# CHRONGLER.net
KiCad netlist of a schematic drawn in EAGLE
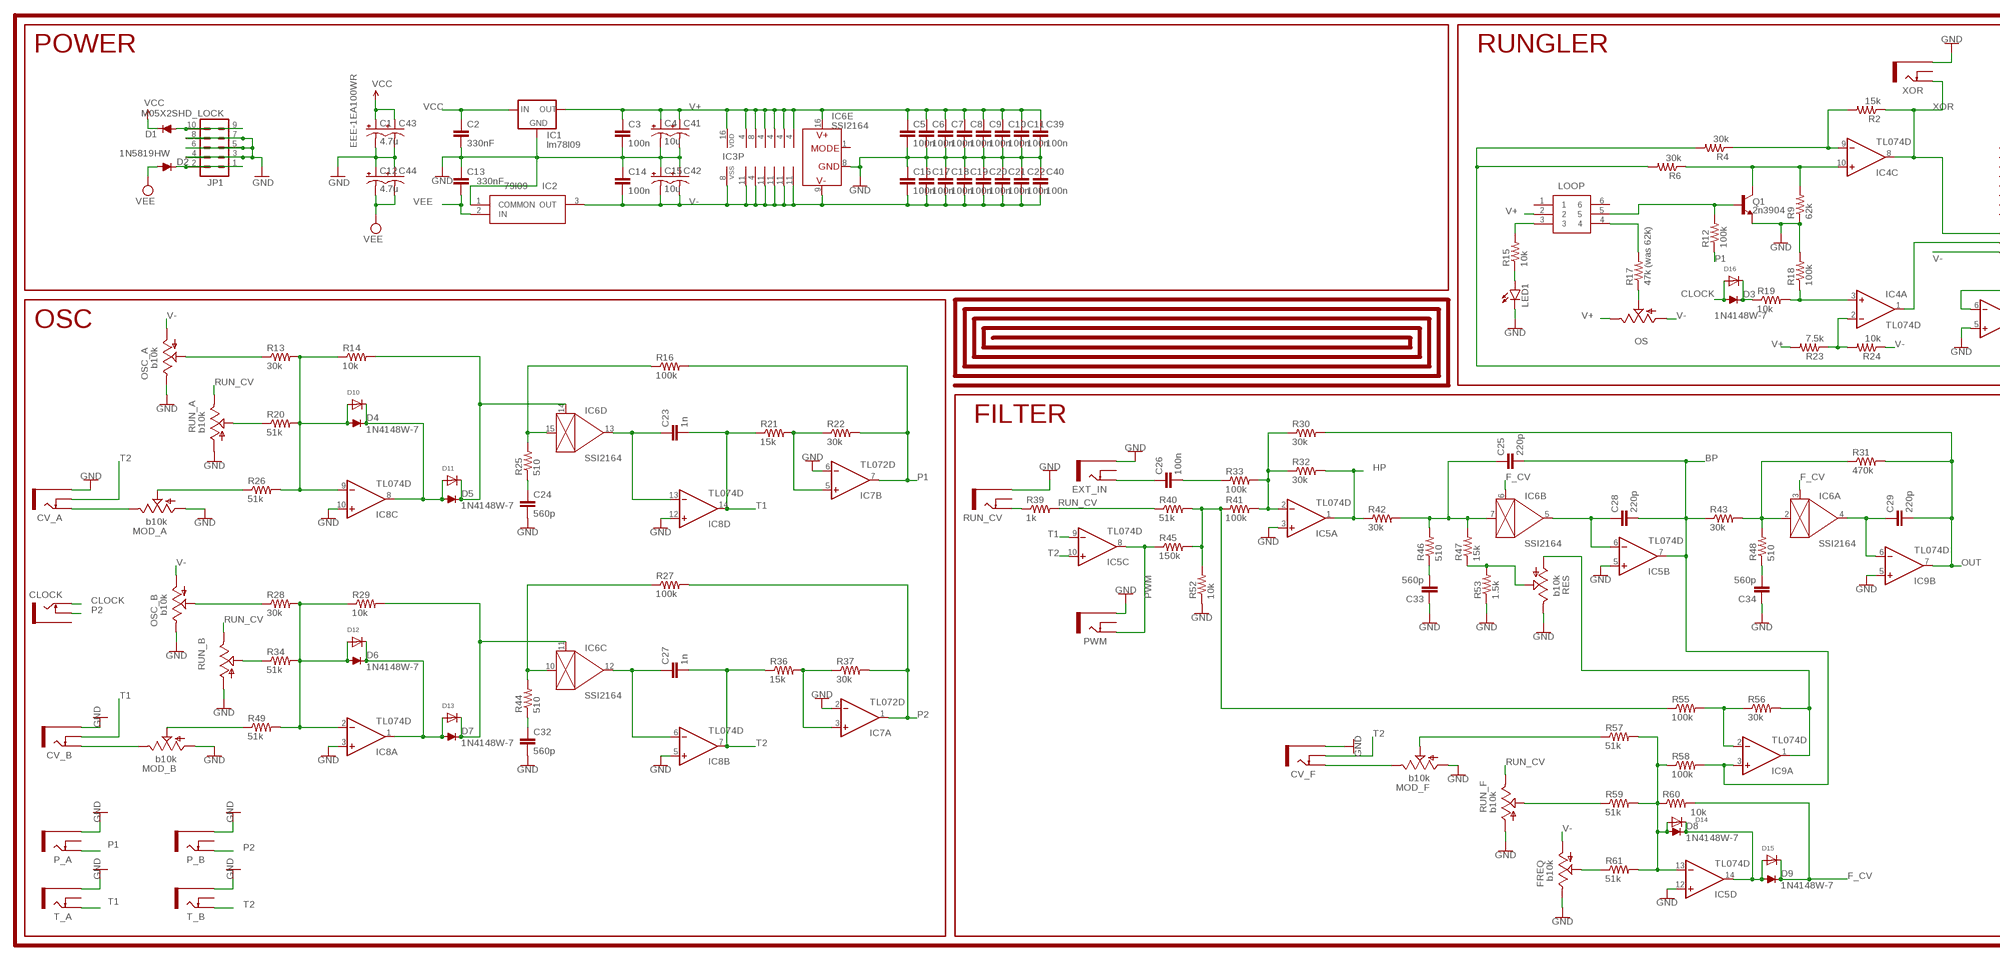
[diagram p0: schematic, sheet 1, part 1 of 2]
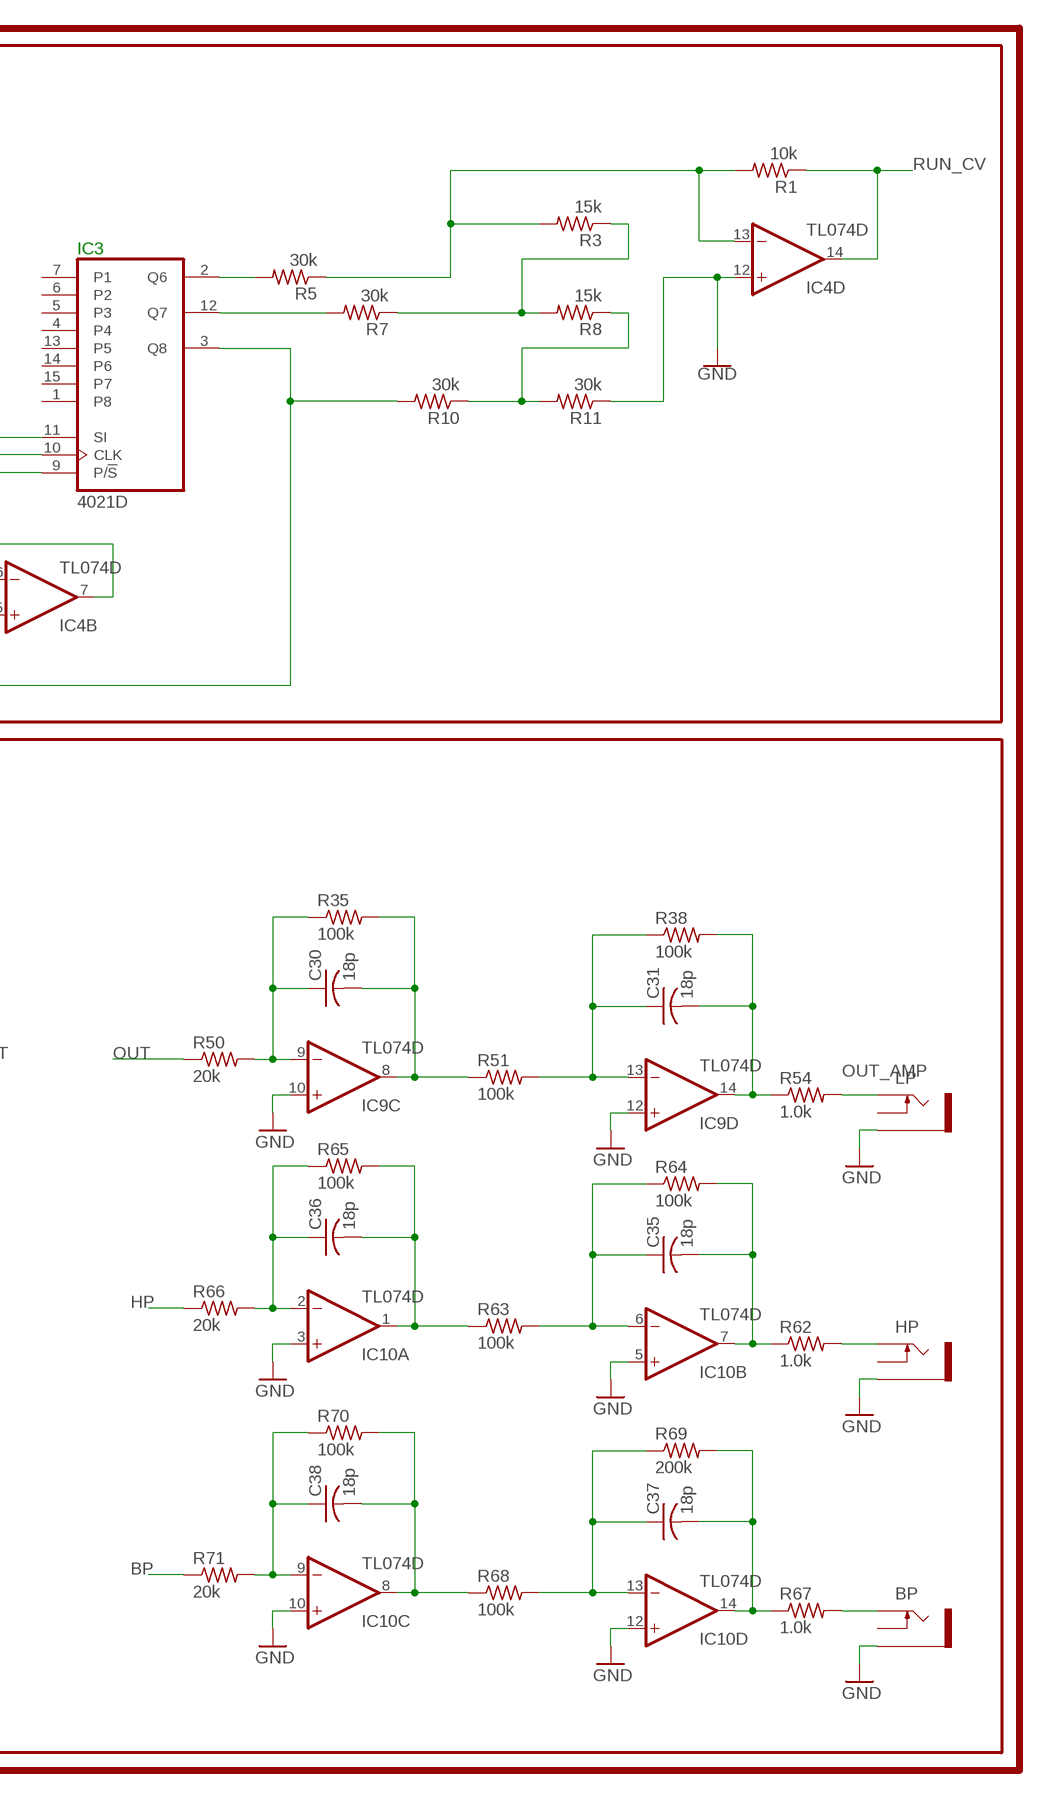
[diagram p1: schematic, sheet 1, part 2 of 2]

(export (version "E")
  (design (tool "Eeschema 10.0.6"))
  (components
    (comp (ref "BP")
      (value "THONKICONNNEW")
      (footprint "eagle-import:WQP-PJ301M-12_JACK")
      (libsource (lib "eagle-import") (part "THONKICONNNEW"))
    )
    (comp (ref "C1")
      (value "4.7u")
      (footprint "eagle-import:PANASONIC_C")
      (libsource (lib "eagle-import") (part "rcl_CPOL-USC"))
    )
    (comp (ref "C2")
      (value "330nF")
      (footprint "eagle-import:C1206")
      (libsource (lib "eagle-import") (part "C-EUC1206"))
    )
    (comp (ref "C3")
      (value "100n")
      (footprint "eagle-import:C1206")
      (libsource (lib "eagle-import") (part "C-EUC1206"))
    )
    (comp (ref "C4")
      (value "10u")
      (footprint "eagle-import:PANASONIC_C")
      (libsource (lib "eagle-import") (part "rcl_CPOL-USC"))
    )
    (comp (ref "C5")
      (value "100n")
      (footprint "eagle-import:C0603")
      (libsource (lib "eagle-import") (part "C-EUC0603"))
    )
    (comp (ref "C6")
      (value "100n")
      (footprint "eagle-import:C0603")
      (libsource (lib "eagle-import") (part "C-EUC0603"))
    )
    (comp (ref "C7")
      (value "100n")
      (footprint "eagle-import:C0603")
      (libsource (lib "eagle-import") (part "C-EUC0603"))
    )
    (comp (ref "C8")
      (value "100n")
      (footprint "eagle-import:C0603")
      (libsource (lib "eagle-import") (part "C-EUC0603"))
    )
    (comp (ref "C9")
      (value "100n")
      (footprint "eagle-import:C0603")
      (libsource (lib "eagle-import") (part "C-EUC0603"))
    )
    (comp (ref "C10")
      (value "100n")
      (footprint "eagle-import:C0603")
      (libsource (lib "eagle-import") (part "C-EUC0603"))
    )
    (comp (ref "C11")
      (value "100n")
      (footprint "eagle-import:C0603")
      (libsource (lib "eagle-import") (part "C-EUC0603"))
    )
    (comp (ref "C12")
      (value "4.7u")
      (footprint "eagle-import:PANASONIC_C")
      (libsource (lib "eagle-import") (part "rcl_CPOL-USC"))
    )
    (comp (ref "C13")
      (value "330nF")
      (footprint "eagle-import:C1206")
      (libsource (lib "eagle-import") (part "C-EUC1206"))
    )
    (comp (ref "C14")
      (value "100n")
      (footprint "eagle-import:C1206")
      (libsource (lib "eagle-import") (part "C-EUC1206"))
    )
    (comp (ref "C15")
      (value "10u")
      (footprint "eagle-import:PANASONIC_C")
      (libsource (lib "eagle-import") (part "rcl_CPOL-USC"))
    )
    (comp (ref "C16")
      (value "100n")
      (footprint "eagle-import:C0603")
      (libsource (lib "eagle-import") (part "C-EUC0603"))
    )
    (comp (ref "C17")
      (value "100n")
      (footprint "eagle-import:C0603")
      (libsource (lib "eagle-import") (part "C-EUC0603"))
    )
    (comp (ref "C18")
      (value "100n")
      (footprint "eagle-import:C0603")
      (libsource (lib "eagle-import") (part "C-EUC0603"))
    )
    (comp (ref "C19")
      (value "100n")
      (footprint "eagle-import:C0603")
      (libsource (lib "eagle-import") (part "C-EUC0603"))
    )
    (comp (ref "C20")
      (value "100n")
      (footprint "eagle-import:C0603")
      (libsource (lib "eagle-import") (part "C-EUC0603"))
    )
    (comp (ref "C21")
      (value "100n")
      (footprint "eagle-import:C0603")
      (libsource (lib "eagle-import") (part "C-EUC0603"))
    )
    (comp (ref "C22")
      (value "100n")
      (footprint "eagle-import:C0603")
      (libsource (lib "eagle-import") (part "C-EUC0603"))
    )
    (comp (ref "C23")
      (value "1n")
      (footprint "eagle-import:C0603")
      (libsource (lib "eagle-import") (part "C-EUC0603"))
    )
    (comp (ref "C24")
      (value "560p")
      (footprint "eagle-import:C0603")
      (libsource (lib "eagle-import") (part "C-EUC0603"))
    )
    (comp (ref "C25")
      (value "220p")
      (footprint "eagle-import:C0603")
      (libsource (lib "eagle-import") (part "C-EUC0603"))
    )
    (comp (ref "C26")
      (value "100n")
      (footprint "eagle-import:C0603")
      (libsource (lib "eagle-import") (part "C-EUC0603"))
    )
    (comp (ref "C27")
      (value "1n")
      (footprint "eagle-import:C0603")
      (libsource (lib "eagle-import") (part "C-EUC0603"))
    )
    (comp (ref "C28")
      (value "220p")
      (footprint "eagle-import:C0603")
      (libsource (lib "eagle-import") (part "C-EUC0603"))
    )
    (comp (ref "C29")
      (value "220p")
      (footprint "eagle-import:C0603")
      (libsource (lib "eagle-import") (part "C-EUC0603"))
    )
    (comp (ref "C30")
      (value "18p")
      (footprint "eagle-import:C0603")
      (libsource (lib "eagle-import") (part "C-USC0603"))
    )
    (comp (ref "C31")
      (value "18p")
      (footprint "eagle-import:C0603")
      (libsource (lib "eagle-import") (part "C-USC0603"))
    )
    (comp (ref "C32")
      (value "560p")
      (footprint "eagle-import:C0603")
      (libsource (lib "eagle-import") (part "C-EUC0603"))
    )
    (comp (ref "C33")
      (value "560p")
      (footprint "eagle-import:C0603")
      (libsource (lib "eagle-import") (part "C-EUC0603"))
    )
    (comp (ref "C34")
      (value "560p")
      (footprint "eagle-import:C0603")
      (libsource (lib "eagle-import") (part "C-EUC0603"))
    )
    (comp (ref "C35")
      (value "18p")
      (footprint "eagle-import:C0603")
      (libsource (lib "eagle-import") (part "C-USC0603"))
    )
    (comp (ref "C36")
      (value "18p")
      (footprint "eagle-import:C0603")
      (libsource (lib "eagle-import") (part "C-USC0603"))
    )
    (comp (ref "C37")
      (value "18p")
      (footprint "eagle-import:C0603")
      (libsource (lib "eagle-import") (part "C-USC0603"))
    )
    (comp (ref "C38")
      (value "18p")
      (footprint "eagle-import:C0603")
      (libsource (lib "eagle-import") (part "C-USC0603"))
    )
    (comp (ref "C39")
      (value "100n")
      (footprint "eagle-import:C0603")
      (libsource (lib "eagle-import") (part "C-EUC0603"))
    )
    (comp (ref "C40")
      (value "100n")
      (footprint "eagle-import:C0603")
      (libsource (lib "eagle-import") (part "C-EUC0603"))
    )
    (comp (ref "C41")
      (value "CPOL-USE2.5-6")
      (footprint "eagle-import:E2,5-6")
      (libsource (lib "eagle-import") (part "CPOL-USE2.5-6"))
    )
    (comp (ref "C42")
      (value "CPOL-USE2.5-6")
      (footprint "eagle-import:E2,5-6")
      (libsource (lib "eagle-import") (part "CPOL-USE2.5-6"))
    )
    (comp (ref "C43")
      (value "CPOL-USE2.5-6")
      (footprint "eagle-import:E2,5-6")
      (libsource (lib "eagle-import") (part "CPOL-USE2.5-6"))
    )
    (comp (ref "C44")
      (value "CPOL-USE2.5-6")
      (footprint "eagle-import:E2,5-6")
      (libsource (lib "eagle-import") (part "CPOL-USE2.5-6"))
    )
    (comp (ref "CLOCK")
      (value "THONKICONNNEW")
      (footprint "eagle-import:WQP-PJ301M-12_JACK")
      (libsource (lib "eagle-import") (part "THONKICONNNEW"))
    )
    (comp (ref "CV_A")
      (value "THONKICONNNEW")
      (footprint "eagle-import:WQP-PJ301M-12_JACK")
      (libsource (lib "eagle-import") (part "THONKICONNNEW"))
    )
    (comp (ref "CV_B")
      (value "THONKICONNNEW")
      (footprint "eagle-import:WQP-PJ301M-12_JACK")
      (libsource (lib "eagle-import") (part "THONKICONNNEW"))
    )
    (comp (ref "CV_F")
      (value "THONKICONNNEW")
      (footprint "eagle-import:WQP-PJ301M-12_JACK")
      (libsource (lib "eagle-import") (part "THONKICONNNEW"))
    )
    (comp (ref "D1")
      (value "1N5819HW")
      (footprint "eagle-import:SOD123")
      (libsource (lib "eagle-import") (part "DIODE-SOD123"))
    )
    (comp (ref "D2")
      (value "1N5819HW")
      (footprint "eagle-import:SOD123")
      (libsource (lib "eagle-import") (part "DIODE-SOD123"))
    )
    (comp (ref "D3")
      (value "1N4148W-7")
      (footprint "eagle-import:SOD123")
      (libsource (lib "eagle-import") (part "1N4148W-7"))
    )
    (comp (ref "D4")
      (value "1N4148W-7")
      (footprint "eagle-import:SOD123")
      (libsource (lib "eagle-import") (part "1N4148W-7"))
    )
    (comp (ref "D5")
      (value "1N4148W-7")
      (footprint "eagle-import:SOD123")
      (libsource (lib "eagle-import") (part "1N4148W-7"))
    )
    (comp (ref "D6")
      (value "1N4148W-7")
      (footprint "eagle-import:SOD123")
      (libsource (lib "eagle-import") (part "1N4148W-7"))
    )
    (comp (ref "D7")
      (value "1N4148W-7")
      (footprint "eagle-import:SOD123")
      (libsource (lib "eagle-import") (part "1N4148W-7"))
    )
    (comp (ref "D8")
      (value "1N4148W-7")
      (footprint "eagle-import:SOD123")
      (libsource (lib "eagle-import") (part "1N4148W-7"))
    )
    (comp (ref "D9")
      (value "1N4148W-7")
      (footprint "eagle-import:SOD123")
      (libsource (lib "eagle-import") (part "1N4148W-7"))
    )
    (comp (ref "D10")
      (value "DIODESOD-323F")
      (footprint "eagle-import:SOD-323F")
      (libsource (lib "eagle-import") (part "DIODESOD-323F"))
    )
    (comp (ref "D11")
      (value "DIODESOD-323F")
      (footprint "eagle-import:SOD-323F")
      (libsource (lib "eagle-import") (part "DIODESOD-323F"))
    )
    (comp (ref "D12")
      (value "DIODESOD-323F")
      (footprint "eagle-import:SOD-323F")
      (libsource (lib "eagle-import") (part "DIODESOD-323F"))
    )
    (comp (ref "D13")
      (value "DIODESOD-323F")
      (footprint "eagle-import:SOD-323F")
      (libsource (lib "eagle-import") (part "DIODESOD-323F"))
    )
    (comp (ref "D14")
      (value "DIODESOD-323F")
      (footprint "eagle-import:SOD-323F")
      (libsource (lib "eagle-import") (part "DIODESOD-323F"))
    )
    (comp (ref "D15")
      (value "DIODESOD-323F")
      (footprint "eagle-import:SOD-323F")
      (libsource (lib "eagle-import") (part "DIODESOD-323F"))
    )
    (comp (ref "D16")
      (value "DIODESOD-323F")
      (footprint "eagle-import:SOD-323F")
      (libsource (lib "eagle-import") (part "DIODESOD-323F"))
    )
    (comp (ref "EXT_IN")
      (value "THONKICONNNEW")
      (footprint "eagle-import:WQP-PJ301M-12_JACK")
      (libsource (lib "eagle-import") (part "THONKICONNNEW"))
    )
    (comp (ref "FREQ")
      (value "b10k")
      (footprint "eagle-import:9MM_SNAP-IN_POT")
      (libsource (lib "eagle-import") (part "9MM_SNAP-IN_POT_"))
    )
    (comp (ref "HP")
      (value "THONKICONNNEW")
      (footprint "eagle-import:WQP-PJ301M-12_JACK")
      (libsource (lib "eagle-import") (part "THONKICONNNEW"))
    )
    (comp (ref "IC1")
      (value "lm78l09")
      (footprint "eagle-import:SOT89")
      (libsource (lib "eagle-import") (part "78LXX-SOT89"))
    )
    (comp (ref "IC2")
      (value "79l09")
      (footprint "eagle-import:SOT-89-3")
      (fields
        (field (name "MANUFACTURER_PART_NUMBER") "NJM79L05UA-TE1")
        (field (name "MOUSER_PART_NUMBER") "513-NJM79L05UA-TE1")
      )
      (libsource (lib "eagle-import") (part "NJM79L05UA-TE1"))
    )
    (comp (ref "IC3")
      (value "4021D")
      (footprint "eagle-import:SO16")
      (libsource (lib "eagle-import") (part "4021D"))
    )
    (comp (ref "IC4")
      (value "TL074D")
      (footprint "eagle-import:SO14")
      (libsource (lib "eagle-import") (part "TL074D"))
    )
    (comp (ref "IC5")
      (value "TL074D")
      (footprint "eagle-import:SO14")
      (libsource (lib "eagle-import") (part "TL074D"))
    )
    (comp (ref "IC6")
      (value "SSI2164")
      (footprint "eagle-import:SOIC16N")
      (libsource (lib "eagle-import") (part "SSM2164S"))
    )
    (comp (ref "IC7")
      (value "TL072D")
      (footprint "eagle-import:SO08")
      (libsource (lib "eagle-import") (part "TL072D"))
    )
    (comp (ref "IC8")
      (value "TL074D")
      (footprint "eagle-import:SO14")
      (libsource (lib "eagle-import") (part "TL074D"))
    )
    (comp (ref "IC9")
      (value "TL074D")
      (footprint "eagle-import:SO14")
      (libsource (lib "eagle-import") (part "TL074D"))
    )
    (comp (ref "IC10")
      (value "TL074D")
      (footprint "eagle-import:SO14")
      (libsource (lib "eagle-import") (part "TL074D"))
    )
    (comp (ref "JP1")
      (value "M05X2SHD_LOCK")
      (footprint "eagle-import:2X5-SHROUDED_LOCK")
      (libsource (lib "eagle-import") (part "M05X2SHD_LOCK"))
    )
    (comp (ref "LED1")
      (value "LEDLD260")
      (footprint "eagle-import:LD260")
      (libsource (lib "eagle-import") (part "LEDLD260"))
    )
    (comp (ref "LOOP")
      (value "MHPS2266")
      (footprint "eagle-import:DIPS450W80P200L600H1050Q6N")
      (fields (field (name "MOUSER_PART_NUMBER") "642-MHPS2266"))
      (libsource (lib "eagle-import") (part "MHPS2266"))
    )
    (comp (ref "LP")
      (value "THONKICONNNEW")
      (footprint "eagle-import:WQP-PJ301M-12_JACK")
      (libsource (lib "eagle-import") (part "THONKICONNNEW"))
    )
    (comp (ref "MOD_A")
      (value "b10k")
      (footprint "eagle-import:9MM_SNAP-IN_POT")
      (libsource (lib "eagle-import") (part "9MM_SNAP-IN_POT_"))
    )
    (comp (ref "MOD_B")
      (value "b10k")
      (footprint "eagle-import:9MM_SNAP-IN_POT")
      (libsource (lib "eagle-import") (part "9MM_SNAP-IN_POT_"))
    )
    (comp (ref "MOD_F")
      (value "b10k")
      (footprint "eagle-import:9MM_SNAP-IN_POT")
      (libsource (lib "eagle-import") (part "9MM_SNAP-IN_POT_"))
    )
    (comp (ref "OS")
      (value "9MM_SNAP-IN_POT_")
      (footprint "eagle-import:9MM_SNAP-IN_POT")
      (libsource (lib "eagle-import") (part "9MM_SNAP-IN_POT_"))
    )
    (comp (ref "OSC_A")
      (value "b10k")
      (footprint "eagle-import:9MM_SNAP-IN_POT")
      (libsource (lib "eagle-import") (part "9MM_SNAP-IN_POT_"))
    )
    (comp (ref "OSC_B")
      (value "b10k")
      (footprint "eagle-import:9MM_SNAP-IN_POT")
      (libsource (lib "eagle-import") (part "9MM_SNAP-IN_POT_"))
    )
    (comp (ref "PWM")
      (value "THONKICONNNEW")
      (footprint "eagle-import:WQP-PJ301M-12_JACK")
      (libsource (lib "eagle-import") (part "THONKICONNNEW"))
    )
    (comp (ref "P_A")
      (value "THONKICONNNEW")
      (footprint "eagle-import:WQP-PJ301M-12_JACK")
      (libsource (lib "eagle-import") (part "THONKICONNNEW"))
    )
    (comp (ref "P_B")
      (value "THONKICONNNEW")
      (footprint "eagle-import:WQP-PJ301M-12_JACK")
      (libsource (lib "eagle-import") (part "THONKICONNNEW"))
    )
    (comp (ref "Q1")
      (value "2n3904")
      (footprint "eagle-import:SOT23-3")
      (libsource (lib "eagle-import") (part "TRANS_NPN-MMBT2222AL"))
    )
    (comp (ref "R1")
      (value "10k")
      (footprint "eagle-import:R0603")
      (libsource (lib "eagle-import") (part "resistor_348_R-US_R0603"))
    )
    (comp (ref "R2")
      (value "15k")
      (footprint "eagle-import:R0603")
      (libsource (lib "eagle-import") (part "resistor_348_R-US_R0603"))
    )
    (comp (ref "R3")
      (value "15k")
      (footprint "eagle-import:R0603")
      (libsource (lib "eagle-import") (part "resistor_348_R-US_R0603"))
    )
    (comp (ref "R4")
      (value "30k")
      (footprint "eagle-import:R0603")
      (libsource (lib "eagle-import") (part "resistor_348_R-US_R0603"))
    )
    (comp (ref "R5")
      (value "30k")
      (footprint "eagle-import:R0603")
      (libsource (lib "eagle-import") (part "resistor_348_R-US_R0603"))
    )
    (comp (ref "R6")
      (value "30k")
      (footprint "eagle-import:R0603")
      (libsource (lib "eagle-import") (part "resistor_348_R-US_R0603"))
    )
    (comp (ref "R7")
      (value "30k")
      (footprint "eagle-import:R0603")
      (libsource (lib "eagle-import") (part "resistor_348_R-US_R0603"))
    )
    (comp (ref "R8")
      (value "15k")
      (footprint "eagle-import:R0603")
      (libsource (lib "eagle-import") (part "resistor_348_R-US_R0603"))
    )
    (comp (ref "R9")
      (value "62k")
      (footprint "eagle-import:R0603")
      (libsource (lib "eagle-import") (part "resistor_348_R-US_R0603"))
    )
    (comp (ref "R10")
      (value "30k")
      (footprint "eagle-import:R0603")
      (libsource (lib "eagle-import") (part "resistor_348_R-US_R0603"))
    )
    (comp (ref "R11")
      (value "30k")
      (footprint "eagle-import:R0603")
      (libsource (lib "eagle-import") (part "resistor_348_R-US_R0603"))
    )
    (comp (ref "R12")
      (value "100k")
      (footprint "eagle-import:R0603")
      (libsource (lib "eagle-import") (part "resistor_348_R-US_R0603"))
    )
    (comp (ref "R13")
      (value "30k")
      (footprint "eagle-import:R0603")
      (libsource (lib "eagle-import") (part "resistor_348_R-US_R0603"))
    )
    (comp (ref "R14")
      (value "10k")
      (footprint "eagle-import:R0603")
      (libsource (lib "eagle-import") (part "resistor_348_R-US_R0603"))
    )
    (comp (ref "R15")
      (value "10k")
      (footprint "eagle-import:R0603")
      (libsource (lib "eagle-import") (part "resistor_348_R-US_R0603"))
    )
    (comp (ref "R16")
      (value "100k")
      (footprint "eagle-import:R0603")
      (libsource (lib "eagle-import") (part "resistor_348_R-US_R0603"))
    )
    (comp (ref "R17")
      (value "47k (was 62k)")
      (footprint "eagle-import:R0603")
      (libsource (lib "eagle-import") (part "resistor_348_R-US_R0603"))
    )
    (comp (ref "R18")
      (value "100k")
      (footprint "eagle-import:R0603")
      (libsource (lib "eagle-import") (part "resistor_348_R-US_R0603"))
    )
    (comp (ref "R19")
      (value "10k")
      (footprint "eagle-import:R0603")
      (libsource (lib "eagle-import") (part "resistor_348_R-US_R0603"))
    )
    (comp (ref "R20")
      (value "51k")
      (footprint "eagle-import:R0603")
      (libsource (lib "eagle-import") (part "resistor_348_R-US_R0603"))
    )
    (comp (ref "R21")
      (value "15k")
      (footprint "eagle-import:R0603")
      (libsource (lib "eagle-import") (part "resistor_348_R-US_R0603"))
    )
    (comp (ref "R22")
      (value "30k")
      (footprint "eagle-import:R0603")
      (libsource (lib "eagle-import") (part "resistor_348_R-US_R0603"))
    )
    (comp (ref "R23")
      (value "7.5k")
      (footprint "eagle-import:R0603")
      (libsource (lib "eagle-import") (part "resistor_348_R-US_R0603"))
    )
    (comp (ref "R24")
      (value "10k")
      (footprint "eagle-import:R0603")
      (libsource (lib "eagle-import") (part "resistor_348_R-US_R0603"))
    )
    (comp (ref "R25")
      (value "510")
      (footprint "eagle-import:R0603")
      (libsource (lib "eagle-import") (part "resistor_348_R-US_R0603"))
    )
    (comp (ref "R26")
      (value "51k")
      (footprint "eagle-import:R0603")
      (libsource (lib "eagle-import") (part "resistor_348_R-US_R0603"))
    )
    (comp (ref "R27")
      (value "100k")
      (footprint "eagle-import:R0603")
      (libsource (lib "eagle-import") (part "resistor_348_R-US_R0603"))
    )
    (comp (ref "R28")
      (value "30k")
      (footprint "eagle-import:R0603")
      (libsource (lib "eagle-import") (part "resistor_348_R-US_R0603"))
    )
    (comp (ref "R29")
      (value "10k")
      (footprint "eagle-import:R0603")
      (libsource (lib "eagle-import") (part "resistor_348_R-US_R0603"))
    )
    (comp (ref "R30")
      (value "30k")
      (footprint "eagle-import:R0603")
      (libsource (lib "eagle-import") (part "resistor_348_R-US_R0603"))
    )
    (comp (ref "R31")
      (value "470k")
      (footprint "eagle-import:R0603")
      (libsource (lib "eagle-import") (part "resistor_348_R-US_R0603"))
    )
    (comp (ref "R32")
      (value "30k")
      (footprint "eagle-import:R0603")
      (libsource (lib "eagle-import") (part "resistor_348_R-US_R0603"))
    )
    (comp (ref "R33")
      (value "100k")
      (footprint "eagle-import:R0603")
      (libsource (lib "eagle-import") (part "resistor_348_R-US_R0603"))
    )
    (comp (ref "R34")
      (value "51k")
      (footprint "eagle-import:R0603")
      (libsource (lib "eagle-import") (part "resistor_348_R-US_R0603"))
    )
    (comp (ref "R35")
      (value "100k")
      (footprint "eagle-import:R0603")
      (libsource (lib "eagle-import") (part "R-US_R0603"))
    )
    (comp (ref "R36")
      (value "15k")
      (footprint "eagle-import:R0603")
      (libsource (lib "eagle-import") (part "resistor_348_R-US_R0603"))
    )
    (comp (ref "R37")
      (value "30k")
      (footprint "eagle-import:R0603")
      (libsource (lib "eagle-import") (part "resistor_348_R-US_R0603"))
    )
    (comp (ref "R38")
      (value "100k")
      (footprint "eagle-import:R0603")
      (libsource (lib "eagle-import") (part "R-US_R0603"))
    )
    (comp (ref "R39")
      (value "1k")
      (footprint "eagle-import:R0603")
      (libsource (lib "eagle-import") (part "resistor_348_R-US_R0603"))
    )
    (comp (ref "R40")
      (value "51k")
      (footprint "eagle-import:R0603")
      (libsource (lib "eagle-import") (part "resistor_348_R-US_R0603"))
    )
    (comp (ref "R41")
      (value "100k")
      (footprint "eagle-import:R0603")
      (libsource (lib "eagle-import") (part "resistor_348_R-US_R0603"))
    )
    (comp (ref "R42")
      (value "30k")
      (footprint "eagle-import:R0603")
      (libsource (lib "eagle-import") (part "resistor_348_R-US_R0603"))
    )
    (comp (ref "R43")
      (value "30k")
      (footprint "eagle-import:R0603")
      (libsource (lib "eagle-import") (part "resistor_348_R-US_R0603"))
    )
    (comp (ref "R44")
      (value "510")
      (footprint "eagle-import:R0603")
      (libsource (lib "eagle-import") (part "resistor_348_R-US_R0603"))
    )
    (comp (ref "R45")
      (value "150k")
      (footprint "eagle-import:R0603")
      (libsource (lib "eagle-import") (part "resistor_348_R-US_R0603"))
    )
    (comp (ref "R46")
      (value "510")
      (footprint "eagle-import:R0603")
      (libsource (lib "eagle-import") (part "resistor_348_R-US_R0603"))
    )
    (comp (ref "R47")
      (value "15k")
      (footprint "eagle-import:R0603")
      (libsource (lib "eagle-import") (part "resistor_348_R-US_R0603"))
    )
    (comp (ref "R48")
      (value "510")
      (footprint "eagle-import:R0603")
      (libsource (lib "eagle-import") (part "resistor_348_R-US_R0603"))
    )
    (comp (ref "R49")
      (value "51k")
      (footprint "eagle-import:R0603")
      (libsource (lib "eagle-import") (part "resistor_348_R-US_R0603"))
    )
    (comp (ref "R50")
      (value "20k")
      (footprint "eagle-import:R0603")
      (libsource (lib "eagle-import") (part "R-US_R0603"))
    )
    (comp (ref "R51")
      (value "100k")
      (footprint "eagle-import:R0603")
      (libsource (lib "eagle-import") (part "R-US_R0603"))
    )
    (comp (ref "R52")
      (value "10k")
      (footprint "eagle-import:R0603")
      (libsource (lib "eagle-import") (part "resistor_348_R-US_R0603"))
    )
    (comp (ref "R53")
      (value "1.5k")
      (footprint "eagle-import:R0603")
      (libsource (lib "eagle-import") (part "resistor_348_R-US_R0603"))
    )
    (comp (ref "R54")
      (value "1.0k")
      (footprint "eagle-import:R0603")
      (libsource (lib "eagle-import") (part "R-US_R0603"))
    )
    (comp (ref "R55")
      (value "100k")
      (footprint "eagle-import:R0603")
      (libsource (lib "eagle-import") (part "resistor_348_R-US_R0603"))
    )
    (comp (ref "R56")
      (value "30k")
      (footprint "eagle-import:R0603")
      (libsource (lib "eagle-import") (part "resistor_348_R-US_R0603"))
    )
    (comp (ref "R57")
      (value "51k")
      (footprint "eagle-import:R0603")
      (libsource (lib "eagle-import") (part "resistor_348_R-US_R0603"))
    )
    (comp (ref "R58")
      (value "100k")
      (footprint "eagle-import:R0603")
      (libsource (lib "eagle-import") (part "resistor_348_R-US_R0603"))
    )
    (comp (ref "R59")
      (value "51k")
      (footprint "eagle-import:R0603")
      (libsource (lib "eagle-import") (part "resistor_348_R-US_R0603"))
    )
    (comp (ref "R60")
      (value "10k")
      (footprint "eagle-import:R0603")
      (libsource (lib "eagle-import") (part "resistor_348_R-US_R0603"))
    )
    (comp (ref "R61")
      (value "51k")
      (footprint "eagle-import:R0603")
      (libsource (lib "eagle-import") (part "resistor_348_R-US_R0603"))
    )
    (comp (ref "R62")
      (value "1.0k")
      (footprint "eagle-import:R0603")
      (libsource (lib "eagle-import") (part "R-US_R0603"))
    )
    (comp (ref "R63")
      (value "100k")
      (footprint "eagle-import:R0603")
      (libsource (lib "eagle-import") (part "R-US_R0603"))
    )
    (comp (ref "R64")
      (value "100k")
      (footprint "eagle-import:R0603")
      (libsource (lib "eagle-import") (part "R-US_R0603"))
    )
    (comp (ref "R65")
      (value "100k")
      (footprint "eagle-import:R0603")
      (libsource (lib "eagle-import") (part "R-US_R0603"))
    )
    (comp (ref "R66")
      (value "20k")
      (footprint "eagle-import:R0603")
      (libsource (lib "eagle-import") (part "R-US_R0603"))
    )
    (comp (ref "R67")
      (value "1.0k")
      (footprint "eagle-import:R0603")
      (libsource (lib "eagle-import") (part "R-US_R0603"))
    )
    (comp (ref "R68")
      (value "100k")
      (footprint "eagle-import:R0603")
      (libsource (lib "eagle-import") (part "R-US_R0603"))
    )
    (comp (ref "R69")
      (value "200k")
      (footprint "eagle-import:R0603")
      (libsource (lib "eagle-import") (part "R-US_R0603"))
    )
    (comp (ref "R70")
      (value "100k")
      (footprint "eagle-import:R0603")
      (libsource (lib "eagle-import") (part "R-US_R0603"))
    )
    (comp (ref "R71")
      (value "20k")
      (footprint "eagle-import:R0603")
      (libsource (lib "eagle-import") (part "R-US_R0603"))
    )
    (comp (ref "RES")
      (value "b10k")
      (footprint "eagle-import:9MM_SNAP-IN_POT")
      (libsource (lib "eagle-import") (part "9MM_SNAP-IN_POT_"))
    )
    (comp (ref "RUN_A")
      (value "b10k")
      (footprint "eagle-import:9MM_SNAP-IN_POT")
      (libsource (lib "eagle-import") (part "9MM_SNAP-IN_POT_"))
    )
    (comp (ref "RUN_B")
      (value "9MM_SNAP-IN_POT_")
      (footprint "eagle-import:9MM_SNAP-IN_POT")
      (libsource (lib "eagle-import") (part "9MM_SNAP-IN_POT_"))
    )
    (comp (ref "RUN_CV")
      (value "THONKICONNNEW")
      (footprint "eagle-import:WQP-PJ301M-12_JACK")
      (libsource (lib "eagle-import") (part "THONKICONNNEW"))
    )
    (comp (ref "RUN_F")
      (value "b10k")
      (footprint "eagle-import:9MM_SNAP-IN_POT")
      (libsource (lib "eagle-import") (part "9MM_SNAP-IN_POT_"))
    )
    (comp (ref "T_A")
      (value "THONKICONNNEW")
      (footprint "eagle-import:WQP-PJ301M-12_JACK")
      (libsource (lib "eagle-import") (part "THONKICONNNEW"))
    )
    (comp (ref "T_B")
      (value "THONKICONNNEW")
      (footprint "eagle-import:WQP-PJ301M-12_JACK")
      (libsource (lib "eagle-import") (part "THONKICONNNEW"))
    )
    (comp (ref "XOR")
      (value "THONKICONNNEW")
      (footprint "eagle-import:WQP-PJ301M-12_JACK")
      (libsource (lib "eagle-import") (part "THONKICONNNEW"))
    )
  )
  (nets
    (net (code "1") (name "/BP") (class "Default")
      (node (ref "C25") (pin "2") (pinfunction "2_2") (pintype "passive"))
      (node (ref "C28") (pin "2") (pinfunction "2_2") (pintype "passive"))
      (node (ref "IC5") (pin "7") (pinfunction "OUT_7") (pintype "output"))
      (node (ref "IC9") (pin "3") (pinfunction "+IN_3") (pintype "input"))
      (node (ref "R43") (pin "1") (pinfunction "1_1") (pintype "passive"))
      (node (ref "R58") (pin "2") (pinfunction "2_2") (pintype "passive"))
      (node (ref "R71") (pin "1") (pinfunction "1_1") (pintype "passive"))
    )
    (net (code "2") (name "/CLOCK") (class "Default")
      (node (ref "CLOCK") (pin "P$1_TIP") (pinfunction "TIP_P$1_TIP") (pintype "passive"))
      (node (ref "D16") (pin "A") (pinfunction "A_A") (pintype "passive"))
      (node (ref "D3") (pin "A") (pinfunction "A_A") (pintype "passive"))
    )
    (net (code "3") (name "/F_CV") (class "Default")
      (node (ref "D15") (pin "C") (pinfunction "C_C") (pintype "passive"))
      (node (ref "D9") (pin "C") (pinfunction "C_C") (pintype "passive"))
      (node (ref "IC6") (pin "3") (pinfunction "CTRL_3") (pintype "input"))
      (node (ref "IC6") (pin "6") (pinfunction "CTRL_6") (pintype "input"))
      (node (ref "R60") (pin "2") (pinfunction "2_2") (pintype "passive"))
    )
    (net (code "4") (name "/HP") (class "Default")
      (node (ref "IC5") (pin "1") (pinfunction "OUT_1") (pintype "output"))
      (node (ref "R32") (pin "2") (pinfunction "2_2") (pintype "passive"))
      (node (ref "R42") (pin "1") (pinfunction "1_1") (pintype "passive"))
      (node (ref "R66") (pin "1") (pinfunction "1_1") (pintype "passive"))
    )
    (net (code "5") (name "/OUT") (class "Default")
      (node (ref "C29") (pin "2") (pinfunction "2_2") (pintype "passive"))
      (node (ref "IC9") (pin "7") (pinfunction "OUT_7") (pintype "output"))
      (node (ref "R30") (pin "2") (pinfunction "2_2") (pintype "passive"))
      (node (ref "R31") (pin "2") (pinfunction "2_2") (pintype "passive"))
      (node (ref "R50") (pin "1") (pinfunction "1_1") (pintype "passive"))
    )
    (net (code "6") (name "/OUT_AMP") (class "Default")
      (node (ref "LP") (pin "P$1_TIP") (pinfunction "TIP_P$1_TIP") (pintype "passive"))
      (node (ref "R54") (pin "2") (pinfunction "2_2") (pintype "passive"))
    )
    (net (code "7") (name "/P1") (class "Default")
      (node (ref "IC7") (pin "7") (pinfunction "OUT_7") (pintype "output"))
      (node (ref "P_A") (pin "P$1_TIP") (pinfunction "TIP_P$1_TIP") (pintype "passive"))
      (node (ref "R12") (pin "1") (pinfunction "1_1") (pintype "passive"))
      (node (ref "R16") (pin "2") (pinfunction "2_2") (pintype "passive"))
      (node (ref "R22") (pin "2") (pinfunction "2_2") (pintype "passive"))
    )
    (net (code "8") (name "/P2") (class "Default")
      (node (ref "CLOCK") (pin "P$2_SWITCH") (pinfunction "SWITCH_P$2_SWITCH") (pintype "passive"))
      (node (ref "IC7") (pin "1") (pinfunction "OUT_1") (pintype "output"))
      (node (ref "P_B") (pin "P$1_TIP") (pinfunction "TIP_P$1_TIP") (pintype "passive"))
      (node (ref "R27") (pin "2") (pinfunction "2_2") (pintype "passive"))
      (node (ref "R37") (pin "2") (pinfunction "2_2") (pintype "passive"))
    )
    (net (code "9") (name "/PWM") (class "Default")
      (node (ref "IC5") (pin "8") (pinfunction "OUT_8") (pintype "output"))
      (node (ref "PWM") (pin "P$1_TIP") (pinfunction "TIP_P$1_TIP") (pintype "passive"))
      (node (ref "R45") (pin "1") (pinfunction "1_1") (pintype "passive"))
    )
    (net (code "10") (name "/RUN_CV") (class "Default")
      (node (ref "IC4") (pin "14") (pinfunction "OUT_14") (pintype "output"))
      (node (ref "R1") (pin "1") (pinfunction "1_1") (pintype "passive"))
      (node (ref "R39") (pin "2") (pinfunction "2_2") (pintype "passive"))
      (node (ref "R40") (pin "1") (pinfunction "1_1") (pintype "passive"))
      (node (ref "RUN_A") (pin "3") (pinfunction "E_3") (pintype "passive"))
      (node (ref "RUN_B") (pin "3") (pinfunction "E_3") (pintype "passive"))
      (node (ref "RUN_F") (pin "3") (pinfunction "E_3") (pintype "passive"))
    )
    (net (code "11") (name "/T1") (class "Default")
      (node (ref "C23") (pin "2") (pinfunction "2_2") (pintype "passive"))
      (node (ref "CV_B") (pin "P$2_SWITCH") (pinfunction "SWITCH_P$2_SWITCH") (pintype "passive"))
      (node (ref "IC5") (pin "9") (pinfunction "-IN_9") (pintype "input"))
      (node (ref "IC8") (pin "14") (pinfunction "OUT_14") (pintype "output"))
      (node (ref "R21") (pin "1") (pinfunction "1_1") (pintype "passive"))
      (node (ref "T_A") (pin "P$1_TIP") (pinfunction "TIP_P$1_TIP") (pintype "passive"))
    )
    (net (code "12") (name "/T2") (class "Default")
      (node (ref "C27") (pin "2") (pinfunction "2_2") (pintype "passive"))
      (node (ref "CV_A") (pin "P$2_SWITCH") (pinfunction "SWITCH_P$2_SWITCH") (pintype "passive"))
      (node (ref "CV_F") (pin "P$2_SWITCH") (pinfunction "SWITCH_P$2_SWITCH") (pintype "passive"))
      (node (ref "IC5") (pin "10") (pinfunction "+IN_10") (pintype "input"))
      (node (ref "IC8") (pin "7") (pinfunction "OUT_7") (pintype "output"))
      (node (ref "R36") (pin "1") (pinfunction "1_1") (pintype "passive"))
      (node (ref "T_B") (pin "P$1_TIP") (pinfunction "TIP_P$1_TIP") (pintype "passive"))
    )
    (net (code "13") (name "/V+") (class "Default")
      (node (ref "C10") (pin "1") (pinfunction "1_1") (pintype "passive"))
      (node (ref "C11") (pin "1") (pinfunction "1_1") (pintype "passive"))
      (node (ref "C3") (pin "1") (pinfunction "1_1") (pintype "passive"))
      (node (ref "C39") (pin "1") (pinfunction "1_1") (pintype "passive"))
      (node (ref "C4") (pin "+") (pinfunction "+_+") (pintype "passive"))
      (node (ref "C41") (pin "+") (pinfunction "+_+") (pintype "passive"))
      (node (ref "C5") (pin "1") (pinfunction "1_1") (pintype "passive"))
      (node (ref "C6") (pin "1") (pinfunction "1_1") (pintype "passive"))
      (node (ref "C7") (pin "1") (pinfunction "1_1") (pintype "passive"))
      (node (ref "C8") (pin "1") (pinfunction "1_1") (pintype "passive"))
      (node (ref "C9") (pin "1") (pinfunction "1_1") (pintype "passive"))
      (node (ref "IC1") (pin "1") (pinfunction "OUT_1") (pintype "passive"))
      (node (ref "IC10") (pin "4") (pinfunction "V+_4") (pintype "power_in"))
      (node (ref "IC3") (pin "16") (pinfunction "VDD_16") (pintype "power_in"))
      (node (ref "IC4") (pin "4") (pinfunction "V+_4") (pintype "power_in"))
      (node (ref "IC5") (pin "4") (pinfunction "V+_4") (pintype "power_in"))
      (node (ref "IC6") (pin "16") (pinfunction "V+_16") (pintype "power_in"))
      (node (ref "IC7") (pin "8") (pinfunction "V+_8") (pintype "power_in"))
      (node (ref "IC8") (pin "4") (pinfunction "V+_4") (pintype "power_in"))
      (node (ref "IC9") (pin "4") (pinfunction "V+_4") (pintype "power_in"))
      (node (ref "LOOP") (pin "2") (pinfunction "2_2") (pintype "bidirectional"))
      (node (ref "OS") (pin "3") (pinfunction "E_3") (pintype "passive"))
      (node (ref "R23") (pin "2") (pinfunction "2_2") (pintype "passive"))
    )
    (net (code "14") (name "/V-") (class "Default")
      (node (ref "C14") (pin "2") (pinfunction "2_2") (pintype "passive"))
      (node (ref "C15") (pin "-") (pinfunction "-_-") (pintype "passive"))
      (node (ref "C16") (pin "2") (pinfunction "2_2") (pintype "passive"))
      (node (ref "C17") (pin "2") (pinfunction "2_2") (pintype "passive"))
      (node (ref "C18") (pin "2") (pinfunction "2_2") (pintype "passive"))
      (node (ref "C19") (pin "2") (pinfunction "2_2") (pintype "passive"))
      (node (ref "C20") (pin "2") (pinfunction "2_2") (pintype "passive"))
      (node (ref "C21") (pin "2") (pinfunction "2_2") (pintype "passive"))
      (node (ref "C22") (pin "2") (pinfunction "2_2") (pintype "passive"))
      (node (ref "C40") (pin "2") (pinfunction "2_2") (pintype "passive"))
      (node (ref "C42") (pin "-") (pinfunction "-_-") (pintype "passive"))
      (node (ref "FREQ") (pin "1") (pinfunction "A_1") (pintype "passive"))
      (node (ref "IC10") (pin "11") (pinfunction "V-_11") (pintype "power_in"))
      (node (ref "IC2") (pin "3") (pinfunction "OUT_3") (pintype "bidirectional"))
      (node (ref "IC3") (pin "8") (pinfunction "VSS_8") (pintype "power_in"))
      (node (ref "IC3") (pin "9") (pinfunction "P/~{S}_9") (pintype "input"))
      (node (ref "IC4") (pin "11") (pinfunction "V-_11") (pintype "power_in"))
      (node (ref "IC5") (pin "11") (pinfunction "V-_11") (pintype "power_in"))
      (node (ref "IC6") (pin "9") (pinfunction "V-_9") (pintype "power_in"))
      (node (ref "IC7") (pin "4") (pinfunction "V-_4") (pintype "power_in"))
      (node (ref "IC8") (pin "11") (pinfunction "V-_11") (pintype "power_in"))
      (node (ref "IC9") (pin "11") (pinfunction "V-_11") (pintype "power_in"))
      (node (ref "OS") (pin "1") (pinfunction "A_1") (pintype "passive"))
      (node (ref "OSC_A") (pin "1") (pinfunction "A_1") (pintype "passive"))
      (node (ref "OSC_B") (pin "1") (pinfunction "A_1") (pintype "passive"))
      (node (ref "R24") (pin "1") (pinfunction "1_1") (pintype "passive"))
    )
    (net (code "15") (name "/XOR") (class "Default")
      (node (ref "IC3") (pin "11") (pinfunction "SI_11") (pintype "input"))
      (node (ref "IC4") (pin "8") (pinfunction "OUT_8") (pintype "output"))
      (node (ref "R2") (pin "1") (pinfunction "1_1") (pintype "passive"))
      (node (ref "XOR") (pin "P$1_TIP") (pinfunction "TIP_P$1_TIP") (pintype "passive"))
    )
    (net (code "16") (name "GND") (class "Default")
      (node (ref "BP") (pin "P$3_SLEEVE") (pinfunction "SLEEVE_P$3_SLEEVE") (pintype "passive"))
      (node (ref "C1") (pin "-") (pinfunction "-_-") (pintype "passive"))
      (node (ref "C10") (pin "2") (pinfunction "2_2") (pintype "passive"))
      (node (ref "C11") (pin "2") (pinfunction "2_2") (pintype "passive"))
      (node (ref "C12") (pin "+") (pinfunction "+_+") (pintype "passive"))
      (node (ref "C13") (pin "1") (pinfunction "1_1") (pintype "passive"))
      (node (ref "C14") (pin "1") (pinfunction "1_1") (pintype "passive"))
      (node (ref "C15") (pin "+") (pinfunction "+_+") (pintype "passive"))
      (node (ref "C16") (pin "1") (pinfunction "1_1") (pintype "passive"))
      (node (ref "C17") (pin "1") (pinfunction "1_1") (pintype "passive"))
      (node (ref "C18") (pin "1") (pinfunction "1_1") (pintype "passive"))
      (node (ref "C19") (pin "1") (pinfunction "1_1") (pintype "passive"))
      (node (ref "C2") (pin "2") (pinfunction "2_2") (pintype "passive"))
      (node (ref "C20") (pin "1") (pinfunction "1_1") (pintype "passive"))
      (node (ref "C21") (pin "1") (pinfunction "1_1") (pintype "passive"))
      (node (ref "C22") (pin "1") (pinfunction "1_1") (pintype "passive"))
      (node (ref "C24") (pin "2") (pinfunction "2_2") (pintype "passive"))
      (node (ref "C3") (pin "2") (pinfunction "2_2") (pintype "passive"))
      (node (ref "C32") (pin "2") (pinfunction "2_2") (pintype "passive"))
      (node (ref "C33") (pin "1") (pinfunction "1_1") (pintype "passive"))
      (node (ref "C34") (pin "1") (pinfunction "1_1") (pintype "passive"))
      (node (ref "C39") (pin "2") (pinfunction "2_2") (pintype "passive"))
      (node (ref "C4") (pin "-") (pinfunction "-_-") (pintype "passive"))
      (node (ref "C40") (pin "1") (pinfunction "1_1") (pintype "passive"))
      (node (ref "C41") (pin "-") (pinfunction "-_-") (pintype "passive"))
      (node (ref "C42") (pin "+") (pinfunction "+_+") (pintype "passive"))
      (node (ref "C43") (pin "-") (pinfunction "-_-") (pintype "passive"))
      (node (ref "C44") (pin "+") (pinfunction "+_+") (pintype "passive"))
      (node (ref "C5") (pin "2") (pinfunction "2_2") (pintype "passive"))
      (node (ref "C6") (pin "2") (pinfunction "2_2") (pintype "passive"))
      (node (ref "C7") (pin "2") (pinfunction "2_2") (pintype "passive"))
      (node (ref "C8") (pin "2") (pinfunction "2_2") (pintype "passive"))
      (node (ref "C9") (pin "2") (pinfunction "2_2") (pintype "passive"))
      (node (ref "CV_A") (pin "P$3_SLEEVE") (pinfunction "SLEEVE_P$3_SLEEVE") (pintype "passive"))
      (node (ref "CV_B") (pin "P$3_SLEEVE") (pinfunction "SLEEVE_P$3_SLEEVE") (pintype "passive"))
      (node (ref "CV_F") (pin "P$3_SLEEVE") (pinfunction "SLEEVE_P$3_SLEEVE") (pintype "passive"))
      (node (ref "EXT_IN") (pin "P$3_SLEEVE") (pinfunction "SLEEVE_P$3_SLEEVE") (pintype "passive"))
      (node (ref "FREQ") (pin "3") (pinfunction "E_3") (pintype "passive"))
      (node (ref "HP") (pin "P$3_SLEEVE") (pinfunction "SLEEVE_P$3_SLEEVE") (pintype "passive"))
      (node (ref "IC1") (pin "2") (pinfunction "GND_2") (pintype "input"))
      (node (ref "IC1") (pin "2@1") (pinfunction "GND_2@1") (pintype "input"))
      (node (ref "IC10") (pin "10") (pinfunction "+IN_10") (pintype "input"))
      (node (ref "IC10") (pin "12") (pinfunction "+IN_12") (pintype "input"))
      (node (ref "IC10") (pin "3") (pinfunction "+IN_3") (pintype "input"))
      (node (ref "IC10") (pin "5") (pinfunction "+IN_5") (pintype "input"))
      (node (ref "IC2") (pin "1") (pinfunction "COMMON_1") (pintype "bidirectional"))
      (node (ref "IC4") (pin "12") (pinfunction "+IN_12") (pintype "input"))
      (node (ref "IC4") (pin "5") (pinfunction "+IN_5") (pintype "input"))
      (node (ref "IC5") (pin "12") (pinfunction "+IN_12") (pintype "input"))
      (node (ref "IC5") (pin "3") (pinfunction "+IN_3") (pintype "input"))
      (node (ref "IC5") (pin "5") (pinfunction "+IN_5") (pintype "input"))
      (node (ref "IC6") (pin "8") (pinfunction "GND_8") (pintype "power_in"))
      (node (ref "IC7") (pin "2") (pinfunction "-IN_2") (pintype "input"))
      (node (ref "IC7") (pin "6") (pinfunction "-IN_6") (pintype "input"))
      (node (ref "IC8") (pin "10") (pinfunction "+IN_10") (pintype "input"))
      (node (ref "IC8") (pin "12") (pinfunction "+IN_12") (pintype "input"))
      (node (ref "IC8") (pin "3") (pinfunction "+IN_3") (pintype "input"))
      (node (ref "IC8") (pin "5") (pinfunction "+IN_5") (pintype "input"))
      (node (ref "IC9") (pin "10") (pinfunction "+IN_10") (pintype "input"))
      (node (ref "IC9") (pin "12") (pinfunction "+IN_12") (pintype "input"))
      (node (ref "IC9") (pin "5") (pinfunction "+IN_5") (pintype "input"))
      (node (ref "JP1") (pin "3") (pinfunction "3_3") (pintype "passive"))
      (node (ref "JP1") (pin "4") (pinfunction "4_4") (pintype "passive"))
      (node (ref "JP1") (pin "5") (pinfunction "5_5") (pintype "passive"))
      (node (ref "JP1") (pin "6") (pinfunction "6_6") (pintype "passive"))
      (node (ref "JP1") (pin "7") (pinfunction "7_7") (pintype "passive"))
      (node (ref "JP1") (pin "8") (pinfunction "8_8") (pintype "passive"))
      (node (ref "LED1") (pin "K") (pinfunction "C_K") (pintype "passive"))
      (node (ref "LP") (pin "P$3_SLEEVE") (pinfunction "SLEEVE_P$3_SLEEVE") (pintype "passive"))
      (node (ref "MOD_A") (pin "1") (pinfunction "A_1") (pintype "passive"))
      (node (ref "MOD_B") (pin "1") (pinfunction "A_1") (pintype "passive"))
      (node (ref "MOD_F") (pin "1") (pinfunction "A_1") (pintype "passive"))
      (node (ref "OSC_A") (pin "3") (pinfunction "E_3") (pintype "passive"))
      (node (ref "OSC_B") (pin "3") (pinfunction "E_3") (pintype "passive"))
      (node (ref "PWM") (pin "P$3_SLEEVE") (pinfunction "SLEEVE_P$3_SLEEVE") (pintype "passive"))
      (node (ref "P_A") (pin "P$3_SLEEVE") (pinfunction "SLEEVE_P$3_SLEEVE") (pintype "passive"))
      (node (ref "P_B") (pin "P$3_SLEEVE") (pinfunction "SLEEVE_P$3_SLEEVE") (pintype "passive"))
      (node (ref "Q1") (pin "2") (pinfunction "E_2") (pintype "passive"))
      (node (ref "R11") (pin "1") (pinfunction "1_1") (pintype "passive"))
      (node (ref "R18") (pin "2") (pinfunction "2_2") (pintype "passive"))
      (node (ref "R52") (pin "1") (pinfunction "1_1") (pintype "passive"))
      (node (ref "R53") (pin "1") (pinfunction "1_1") (pintype "passive"))
      (node (ref "R9") (pin "1") (pinfunction "1_1") (pintype "passive"))
      (node (ref "RES") (pin "3") (pinfunction "E_3") (pintype "passive"))
      (node (ref "RUN_A") (pin "1") (pinfunction "A_1") (pintype "passive"))
      (node (ref "RUN_B") (pin "1") (pinfunction "A_1") (pintype "passive"))
      (node (ref "RUN_CV") (pin "P$3_SLEEVE") (pinfunction "SLEEVE_P$3_SLEEVE") (pintype "passive"))
      (node (ref "RUN_F") (pin "1") (pinfunction "A_1") (pintype "passive"))
      (node (ref "T_A") (pin "P$3_SLEEVE") (pinfunction "SLEEVE_P$3_SLEEVE") (pintype "passive"))
      (node (ref "T_B") (pin "P$3_SLEEVE") (pinfunction "SLEEVE_P$3_SLEEVE") (pintype "passive"))
      (node (ref "XOR") (pin "P$3_SLEEVE") (pinfunction "SLEEVE_P$3_SLEEVE") (pintype "passive"))
    )
    (net (code "17") (name "Net-(BP-TIP)") (class "Default")
      (node (ref "BP") (pin "P$1_TIP") (pinfunction "TIP_P$1_TIP") (pintype "passive"))
      (node (ref "R67") (pin "2") (pinfunction "2_2") (pintype "passive"))
    )
    (net (code "18") (name "Net-(C24-Pad1)") (class "Default")
      (node (ref "C24") (pin "1") (pinfunction "1_1") (pintype "passive"))
      (node (ref "R25") (pin "1") (pinfunction "1_1") (pintype "passive"))
    )
    (net (code "19") (name "Net-(C26-Pad2)") (class "Default")
      (node (ref "C26") (pin "2") (pinfunction "2_2") (pintype "passive"))
      (node (ref "R33") (pin "1") (pinfunction "1_1") (pintype "passive"))
    )
    (net (code "20") (name "Net-(C32-Pad1)") (class "Default")
      (node (ref "C32") (pin "1") (pinfunction "1_1") (pintype "passive"))
      (node (ref "R44") (pin "1") (pinfunction "1_1") (pintype "passive"))
    )
    (net (code "21") (name "Net-(C33-Pad2)") (class "Default")
      (node (ref "C33") (pin "2") (pinfunction "2_2") (pintype "passive"))
      (node (ref "R46") (pin "1") (pinfunction "1_1") (pintype "passive"))
    )
    (net (code "22") (name "Net-(C34-Pad2)") (class "Default")
      (node (ref "C34") (pin "2") (pinfunction "2_2") (pintype "passive"))
      (node (ref "R48") (pin "1") (pinfunction "1_1") (pintype "passive"))
    )
    (net (code "23") (name "Net-(CV_A-TIP)") (class "Default")
      (node (ref "CV_A") (pin "P$1_TIP") (pinfunction "TIP_P$1_TIP") (pintype "passive"))
      (node (ref "MOD_A") (pin "3") (pinfunction "E_3") (pintype "passive"))
    )
    (net (code "24") (name "Net-(CV_B-TIP)") (class "Default")
      (node (ref "CV_B") (pin "P$1_TIP") (pinfunction "TIP_P$1_TIP") (pintype "passive"))
      (node (ref "MOD_B") (pin "3") (pinfunction "E_3") (pintype "passive"))
    )
    (net (code "25") (name "Net-(CV_F-TIP)") (class "Default")
      (node (ref "CV_F") (pin "P$1_TIP") (pinfunction "TIP_P$1_TIP") (pintype "passive"))
      (node (ref "MOD_F") (pin "3") (pinfunction "E_3") (pintype "passive"))
    )
    (net (code "26") (name "Net-(D1-PadA)") (class "Default")
      (node (ref "D1") (pin "A") (pinfunction "A_A") (pintype "passive"))
      (node (ref "JP1") (pin "10") (pinfunction "10_10") (pintype "passive"))
      (node (ref "JP1") (pin "9") (pinfunction "9_9") (pintype "passive"))
    )
    (net (code "27") (name "Net-(D2-PadC)") (class "Default")
      (node (ref "D2") (pin "C") (pinfunction "C_C") (pintype "passive"))
      (node (ref "JP1") (pin "1") (pinfunction "1_1") (pintype "passive"))
      (node (ref "JP1") (pin "2") (pinfunction "2_2") (pintype "passive"))
    )
    (net (code "28") (name "Net-(D16-PadC)") (class "Default")
      (node (ref "D16") (pin "C") (pinfunction "C_C") (pintype "passive"))
      (node (ref "D3") (pin "C") (pinfunction "C_C") (pintype "passive"))
      (node (ref "R19") (pin "1") (pinfunction "1_1") (pintype "passive"))
    )
    (net (code "29") (name "Net-(EXT_IN-TIP)") (class "Default")
      (node (ref "C26") (pin "1") (pinfunction "1_1") (pintype "passive"))
      (node (ref "EXT_IN") (pin "P$1_TIP") (pinfunction "TIP_P$1_TIP") (pintype "passive"))
    )
    (net (code "30") (name "Net-(FREQ-S)") (class "Default")
      (node (ref "FREQ") (pin "2") (pinfunction "S_2") (pintype "passive"))
      (node (ref "R61") (pin "1") (pinfunction "1_1") (pintype "passive"))
    )
    (net (code "31") (name "Net-(HP-TIP)") (class "Default")
      (node (ref "HP") (pin "P$1_TIP") (pinfunction "TIP_P$1_TIP") (pintype "passive"))
      (node (ref "R62") (pin "2") (pinfunction "2_2") (pintype "passive"))
    )
    (net (code "32") (name "Net-(IC3A-CLK)") (class "Default")
      (node (ref "IC3") (pin "10") (pinfunction "CLK_10") (pintype "input"))
      (node (ref "IC4") (pin "1") (pinfunction "OUT_1") (pintype "output"))
    )
    (net (code "33") (name "Net-(IC3A-Q6)") (class "Default")
      (node (ref "IC3") (pin "2") (pinfunction "Q6_2") (pintype "output"))
      (node (ref "R5") (pin "2") (pinfunction "2_2") (pintype "passive"))
    )
    (net (code "34") (name "Net-(IC3A-Q7)") (class "Default")
      (node (ref "IC3") (pin "12") (pinfunction "Q7_12") (pintype "output"))
      (node (ref "R7") (pin "2") (pinfunction "2_2") (pintype "passive"))
    )
    (net (code "35") (name "Net-(IC3A-Q8)") (class "Default")
      (node (ref "IC3") (pin "3") (pinfunction "Q8_3") (pintype "output"))
      (node (ref "R10") (pin "2") (pinfunction "2_2") (pintype "passive"))
      (node (ref "R4") (pin "2") (pinfunction "2_2") (pintype "passive"))
      (node (ref "R6") (pin "2") (pinfunction "2_2") (pintype "passive"))
    )
    (net (code "36") (name "Net-(IC4A-+IN)") (class "Default")
      (node (ref "IC4") (pin "3") (pinfunction "+IN_3") (pintype "input"))
      (node (ref "R18") (pin "1") (pinfunction "1_1") (pintype "passive"))
      (node (ref "R19") (pin "2") (pinfunction "2_2") (pintype "passive"))
    )
    (net (code "37") (name "Net-(IC4A--IN)") (class "Default")
      (node (ref "IC4") (pin "2") (pinfunction "-IN_2") (pintype "input"))
      (node (ref "R23") (pin "1") (pinfunction "1_1") (pintype "passive"))
      (node (ref "R24") (pin "2") (pinfunction "2_2") (pintype "passive"))
    )
    (net (code "38") (name "Net-(IC4B--IN)") (class "Default")
      (node (ref "IC4") (pin "6") (pinfunction "-IN_6") (pintype "input"))
      (node (ref "IC4") (pin "7") (pinfunction "OUT_7") (pintype "output"))
    )
    (net (code "39") (name "Net-(IC4C-+IN)") (class "Default")
      (node (ref "IC4") (pin "10") (pinfunction "+IN_10") (pintype "input"))
      (node (ref "Q1") (pin "3") (pinfunction "C_3") (pintype "passive"))
      (node (ref "R6") (pin "1") (pinfunction "1_1") (pintype "passive"))
      (node (ref "R9") (pin "2") (pinfunction "2_2") (pintype "passive"))
    )
    (net (code "40") (name "Net-(IC4C--IN)") (class "Default")
      (node (ref "IC4") (pin "9") (pinfunction "-IN_9") (pintype "input"))
      (node (ref "R2") (pin "2") (pinfunction "2_2") (pintype "passive"))
      (node (ref "R4") (pin "1") (pinfunction "1_1") (pintype "passive"))
    )
    (net (code "41") (name "Net-(IC4D--IN)") (class "Default")
      (node (ref "IC4") (pin "13") (pinfunction "-IN_13") (pintype "input"))
      (node (ref "R1") (pin "2") (pinfunction "2_2") (pintype "passive"))
      (node (ref "R3") (pin "2") (pinfunction "2_2") (pintype "passive"))
      (node (ref "R5") (pin "1") (pinfunction "1_1") (pintype "passive"))
    )
    (net (code "42") (name "Net-(IC5A--IN)") (class "Default")
      (node (ref "IC5") (pin "2") (pinfunction "-IN_2") (pintype "input"))
      (node (ref "R30") (pin "1") (pinfunction "1_1") (pintype "passive"))
      (node (ref "R32") (pin "1") (pinfunction "1_1") (pintype "passive"))
      (node (ref "R33") (pin "2") (pinfunction "2_2") (pintype "passive"))
      (node (ref "R41") (pin "2") (pinfunction "2_2") (pintype "passive"))
    )
    (net (code "43") (name "Net-(IC5B--IN)") (class "Default")
      (node (ref "C28") (pin "1") (pinfunction "1_1") (pintype "passive"))
      (node (ref "IC5") (pin "6") (pinfunction "-IN_6") (pintype "input"))
      (node (ref "IC6") (pin "5") (pinfunction "OUT_5") (pintype "output"))
    )
    (net (code "44") (name "Net-(IC5D--IN)") (class "Default")
      (node (ref "D14") (pin "A") (pinfunction "A_A") (pintype "passive"))
      (node (ref "D8") (pin "A") (pinfunction "A_A") (pintype "passive"))
      (node (ref "IC5") (pin "13") (pinfunction "-IN_13") (pintype "input"))
      (node (ref "R57") (pin "2") (pinfunction "2_2") (pintype "passive"))
      (node (ref "R58") (pin "1") (pinfunction "1_1") (pintype "passive"))
      (node (ref "R59") (pin "2") (pinfunction "2_2") (pintype "passive"))
      (node (ref "R60") (pin "1") (pinfunction "1_1") (pintype "passive"))
      (node (ref "R61") (pin "2") (pinfunction "2_2") (pintype "passive"))
    )
    (net (code "45") (name "Net-(IC5D-OUT)") (class "Default")
      (node (ref "D14") (pin "C") (pinfunction "C_C") (pintype "passive"))
      (node (ref "D15") (pin "A") (pinfunction "A_A") (pintype "passive"))
      (node (ref "D8") (pin "C") (pinfunction "C_C") (pintype "passive"))
      (node (ref "D9") (pin "A") (pinfunction "A_A") (pintype "passive"))
      (node (ref "IC5") (pin "14") (pinfunction "OUT_14") (pintype "output"))
    )
    (net (code "46") (name "Net-(IC6A-IN)") (class "Default")
      (node (ref "IC6") (pin "2") (pinfunction "IN_2") (pintype "input"))
      (node (ref "R31") (pin "1") (pinfunction "1_1") (pintype "passive"))
      (node (ref "R43") (pin "2") (pinfunction "2_2") (pintype "passive"))
      (node (ref "R48") (pin "2") (pinfunction "2_2") (pintype "passive"))
    )
    (net (code "47") (name "Net-(IC6A-OUT)") (class "Default")
      (node (ref "C29") (pin "1") (pinfunction "1_1") (pintype "passive"))
      (node (ref "IC6") (pin "4") (pinfunction "OUT_4") (pintype "output"))
      (node (ref "IC9") (pin "6") (pinfunction "-IN_6") (pintype "input"))
    )
    (net (code "48") (name "Net-(IC6B-IN)") (class "Default")
      (node (ref "C25") (pin "1") (pinfunction "1_1") (pintype "passive"))
      (node (ref "IC6") (pin "7") (pinfunction "IN_7") (pintype "input"))
      (node (ref "R42") (pin "2") (pinfunction "2_2") (pintype "passive"))
      (node (ref "R46") (pin "2") (pinfunction "2_2") (pintype "passive"))
      (node (ref "R47") (pin "2") (pinfunction "2_2") (pintype "passive"))
    )
    (net (code "49") (name "Net-(IC6C-CTRL)") (class "Default")
      (node (ref "D13") (pin "C") (pinfunction "C_C") (pintype "passive"))
      (node (ref "D7") (pin "C") (pinfunction "C_C") (pintype "passive"))
      (node (ref "IC6") (pin "11") (pinfunction "CTRL_11") (pintype "input"))
      (node (ref "R29") (pin "2") (pinfunction "2_2") (pintype "passive"))
    )
    (net (code "50") (name "Net-(IC6C-IN)") (class "Default")
      (node (ref "IC6") (pin "10") (pinfunction "IN_10") (pintype "input"))
      (node (ref "R27") (pin "1") (pinfunction "1_1") (pintype "passive"))
      (node (ref "R44") (pin "2") (pinfunction "2_2") (pintype "passive"))
    )
    (net (code "51") (name "Net-(IC6C-OUT)") (class "Default")
      (node (ref "C27") (pin "1") (pinfunction "1_1") (pintype "passive"))
      (node (ref "IC6") (pin "12") (pinfunction "OUT_12") (pintype "output"))
      (node (ref "IC8") (pin "6") (pinfunction "-IN_6") (pintype "input"))
    )
    (net (code "52") (name "Net-(IC6D-CTRL)") (class "Default")
      (node (ref "D11") (pin "C") (pinfunction "C_C") (pintype "passive"))
      (node (ref "D5") (pin "C") (pinfunction "C_C") (pintype "passive"))
      (node (ref "IC6") (pin "14") (pinfunction "CTRL_14") (pintype "input"))
      (node (ref "R14") (pin "2") (pinfunction "2_2") (pintype "passive"))
    )
    (net (code "53") (name "Net-(IC6D-IN)") (class "Default")
      (node (ref "IC6") (pin "15") (pinfunction "IN_15") (pintype "input"))
      (node (ref "R16") (pin "1") (pinfunction "1_1") (pintype "passive"))
      (node (ref "R25") (pin "2") (pinfunction "2_2") (pintype "passive"))
    )
    (net (code "54") (name "Net-(IC6D-OUT)") (class "Default")
      (node (ref "C23") (pin "1") (pinfunction "1_1") (pintype "passive"))
      (node (ref "IC6") (pin "13") (pinfunction "OUT_13") (pintype "output"))
      (node (ref "IC8") (pin "13") (pinfunction "-IN_13") (pintype "input"))
    )
    (net (code "55") (name "Net-(IC7A-+IN)") (class "Default")
      (node (ref "IC7") (pin "3") (pinfunction "+IN_3") (pintype "input"))
      (node (ref "R36") (pin "2") (pinfunction "2_2") (pintype "passive"))
      (node (ref "R37") (pin "1") (pinfunction "1_1") (pintype "passive"))
    )
    (net (code "56") (name "Net-(IC7B-+IN)") (class "Default")
      (node (ref "IC7") (pin "5") (pinfunction "+IN_5") (pintype "input"))
      (node (ref "R21") (pin "2") (pinfunction "2_2") (pintype "passive"))
      (node (ref "R22") (pin "1") (pinfunction "1_1") (pintype "passive"))
    )
    (net (code "57") (name "Net-(IC8A--IN)") (class "Default")
      (node (ref "D12") (pin "A") (pinfunction "A_A") (pintype "passive"))
      (node (ref "D6") (pin "A") (pinfunction "A_A") (pintype "passive"))
      (node (ref "IC8") (pin "2") (pinfunction "-IN_2") (pintype "input"))
      (node (ref "R28") (pin "2") (pinfunction "2_2") (pintype "passive"))
      (node (ref "R29") (pin "1") (pinfunction "1_1") (pintype "passive"))
      (node (ref "R34") (pin "2") (pinfunction "2_2") (pintype "passive"))
      (node (ref "R49") (pin "2") (pinfunction "2_2") (pintype "passive"))
    )
    (net (code "58") (name "Net-(IC8A-OUT)") (class "Default")
      (node (ref "D12") (pin "C") (pinfunction "C_C") (pintype "passive"))
      (node (ref "D13") (pin "A") (pinfunction "A_A") (pintype "passive"))
      (node (ref "D6") (pin "C") (pinfunction "C_C") (pintype "passive"))
      (node (ref "D7") (pin "A") (pinfunction "A_A") (pintype "passive"))
      (node (ref "IC8") (pin "1") (pinfunction "OUT_1") (pintype "output"))
    )
    (net (code "59") (name "Net-(IC8C--IN)") (class "Default")
      (node (ref "D10") (pin "A") (pinfunction "A_A") (pintype "passive"))
      (node (ref "D4") (pin "A") (pinfunction "A_A") (pintype "passive"))
      (node (ref "IC8") (pin "9") (pinfunction "-IN_9") (pintype "input"))
      (node (ref "R13") (pin "2") (pinfunction "2_2") (pintype "passive"))
      (node (ref "R14") (pin "1") (pinfunction "1_1") (pintype "passive"))
      (node (ref "R20") (pin "2") (pinfunction "2_2") (pintype "passive"))
      (node (ref "R26") (pin "2") (pinfunction "2_2") (pintype "passive"))
    )
    (net (code "60") (name "Net-(IC8C-OUT)") (class "Default")
      (node (ref "D10") (pin "C") (pinfunction "C_C") (pintype "passive"))
      (node (ref "D11") (pin "A") (pinfunction "A_A") (pintype "passive"))
      (node (ref "D4") (pin "C") (pinfunction "C_C") (pintype "passive"))
      (node (ref "D5") (pin "A") (pinfunction "A_A") (pintype "passive"))
      (node (ref "IC8") (pin "8") (pinfunction "OUT_8") (pintype "output"))
    )
    (net (code "61") (name "Net-(IC9A--IN)") (class "Default")
      (node (ref "IC9") (pin "2") (pinfunction "-IN_2") (pintype "input"))
      (node (ref "R55") (pin "2") (pinfunction "2_2") (pintype "passive"))
      (node (ref "R56") (pin "1") (pinfunction "1_1") (pintype "passive"))
    )
    (net (code "62") (name "Net-(IC9A-OUT)") (class "Default")
      (node (ref "IC9") (pin "1") (pinfunction "OUT_1") (pintype "output"))
      (node (ref "R56") (pin "2") (pinfunction "2_2") (pintype "passive"))
      (node (ref "RES") (pin "1") (pinfunction "A_1") (pintype "passive"))
    )
    (net (code "63") (name "Net-(IC9C--IN)") (class "Default")
      (node (ref "C30") (pin "1") (pinfunction "1_1") (pintype "passive"))
      (node (ref "IC9") (pin "9") (pinfunction "-IN_9") (pintype "input"))
      (node (ref "R35") (pin "1") (pinfunction "1_1") (pintype "passive"))
      (node (ref "R50") (pin "2") (pinfunction "2_2") (pintype "passive"))
    )
    (net (code "64") (name "Net-(IC9C-OUT)") (class "Default")
      (node (ref "C30") (pin "2") (pinfunction "2_2") (pintype "passive"))
      (node (ref "IC9") (pin "8") (pinfunction "OUT_8") (pintype "output"))
      (node (ref "R35") (pin "2") (pinfunction "2_2") (pintype "passive"))
      (node (ref "R51") (pin "1") (pinfunction "1_1") (pintype "passive"))
    )
    (net (code "65") (name "Net-(IC9D--IN)") (class "Default")
      (node (ref "C31") (pin "1") (pinfunction "1_1") (pintype "passive"))
      (node (ref "IC9") (pin "13") (pinfunction "-IN_13") (pintype "input"))
      (node (ref "R38") (pin "1") (pinfunction "1_1") (pintype "passive"))
      (node (ref "R51") (pin "2") (pinfunction "2_2") (pintype "passive"))
    )
    (net (code "66") (name "Net-(IC9D-OUT)") (class "Default")
      (node (ref "C31") (pin "2") (pinfunction "2_2") (pintype "passive"))
      (node (ref "IC9") (pin "14") (pinfunction "OUT_14") (pintype "output"))
      (node (ref "R38") (pin "2") (pinfunction "2_2") (pintype "passive"))
      (node (ref "R54") (pin "1") (pinfunction "1_1") (pintype "passive"))
    )
    (net (code "67") (name "Net-(IC10A--IN)") (class "Default")
      (node (ref "C36") (pin "1") (pinfunction "1_1") (pintype "passive"))
      (node (ref "IC10") (pin "2") (pinfunction "-IN_2") (pintype "input"))
      (node (ref "R65") (pin "1") (pinfunction "1_1") (pintype "passive"))
      (node (ref "R66") (pin "2") (pinfunction "2_2") (pintype "passive"))
    )
    (net (code "68") (name "Net-(IC10A-OUT)") (class "Default")
      (node (ref "C36") (pin "2") (pinfunction "2_2") (pintype "passive"))
      (node (ref "IC10") (pin "1") (pinfunction "OUT_1") (pintype "output"))
      (node (ref "R63") (pin "1") (pinfunction "1_1") (pintype "passive"))
      (node (ref "R65") (pin "2") (pinfunction "2_2") (pintype "passive"))
    )
    (net (code "69") (name "Net-(IC10B--IN)") (class "Default")
      (node (ref "C35") (pin "1") (pinfunction "1_1") (pintype "passive"))
      (node (ref "IC10") (pin "6") (pinfunction "-IN_6") (pintype "input"))
      (node (ref "R63") (pin "2") (pinfunction "2_2") (pintype "passive"))
      (node (ref "R64") (pin "1") (pinfunction "1_1") (pintype "passive"))
    )
    (net (code "70") (name "Net-(IC10B-OUT)") (class "Default")
      (node (ref "C35") (pin "2") (pinfunction "2_2") (pintype "passive"))
      (node (ref "IC10") (pin "7") (pinfunction "OUT_7") (pintype "output"))
      (node (ref "R62") (pin "1") (pinfunction "1_1") (pintype "passive"))
      (node (ref "R64") (pin "2") (pinfunction "2_2") (pintype "passive"))
    )
    (net (code "71") (name "Net-(IC10C--IN)") (class "Default")
      (node (ref "C38") (pin "1") (pinfunction "1_1") (pintype "passive"))
      (node (ref "IC10") (pin "9") (pinfunction "-IN_9") (pintype "input"))
      (node (ref "R70") (pin "1") (pinfunction "1_1") (pintype "passive"))
      (node (ref "R71") (pin "2") (pinfunction "2_2") (pintype "passive"))
    )
    (net (code "72") (name "Net-(IC10C-OUT)") (class "Default")
      (node (ref "C38") (pin "2") (pinfunction "2_2") (pintype "passive"))
      (node (ref "IC10") (pin "8") (pinfunction "OUT_8") (pintype "output"))
      (node (ref "R68") (pin "1") (pinfunction "1_1") (pintype "passive"))
      (node (ref "R70") (pin "2") (pinfunction "2_2") (pintype "passive"))
    )
    (net (code "73") (name "Net-(IC10D--IN)") (class "Default")
      (node (ref "C37") (pin "1") (pinfunction "1_1") (pintype "passive"))
      (node (ref "IC10") (pin "13") (pinfunction "-IN_13") (pintype "input"))
      (node (ref "R68") (pin "2") (pinfunction "2_2") (pintype "passive"))
      (node (ref "R69") (pin "1") (pinfunction "1_1") (pintype "passive"))
    )
    (net (code "74") (name "Net-(IC10D-OUT)") (class "Default")
      (node (ref "C37") (pin "2") (pinfunction "2_2") (pintype "passive"))
      (node (ref "IC10") (pin "14") (pinfunction "OUT_14") (pintype "output"))
      (node (ref "R67") (pin "1") (pinfunction "1_1") (pintype "passive"))
      (node (ref "R69") (pin "2") (pinfunction "2_2") (pintype "passive"))
    )
    (net (code "75") (name "Net-(LED1-PadA)") (class "Default")
      (node (ref "LED1") (pin "A") (pinfunction "A_A") (pintype "passive"))
      (node (ref "R15") (pin "1") (pinfunction "1_1") (pintype "passive"))
    )
    (net (code "76") (name "Net-(LOOP-Pad3)") (class "Default")
      (node (ref "LOOP") (pin "3") (pinfunction "3_3") (pintype "bidirectional"))
      (node (ref "R15") (pin "2") (pinfunction "2_2") (pintype "passive"))
    )
    (net (code "77") (name "Net-(LOOP-Pad4)") (class "Default")
      (node (ref "LOOP") (pin "4") (pinfunction "4_4") (pintype "bidirectional"))
      (node (ref "R17") (pin "2") (pinfunction "2_2") (pintype "passive"))
    )
    (net (code "78") (name "Net-(MOD_A-S)") (class "Default")
      (node (ref "MOD_A") (pin "2") (pinfunction "S_2") (pintype "passive"))
      (node (ref "R26") (pin "1") (pinfunction "1_1") (pintype "passive"))
    )
    (net (code "79") (name "Net-(MOD_B-S)") (class "Default")
      (node (ref "MOD_B") (pin "2") (pinfunction "S_2") (pintype "passive"))
      (node (ref "R49") (pin "1") (pinfunction "1_1") (pintype "passive"))
    )
    (net (code "80") (name "Net-(MOD_F-S)") (class "Default")
      (node (ref "MOD_F") (pin "2") (pinfunction "S_2") (pintype "passive"))
      (node (ref "R57") (pin "1") (pinfunction "1_1") (pintype "passive"))
    )
    (net (code "81") (name "Net-(OS-S)") (class "Default")
      (node (ref "OS") (pin "2") (pinfunction "S_2") (pintype "passive"))
      (node (ref "R17") (pin "1") (pinfunction "1_1") (pintype "passive"))
    )
    (net (code "82") (name "Net-(OSC_A-S)") (class "Default")
      (node (ref "OSC_A") (pin "2") (pinfunction "S_2") (pintype "passive"))
      (node (ref "R13") (pin "1") (pinfunction "1_1") (pintype "passive"))
    )
    (net (code "83") (name "Net-(OSC_B-S)") (class "Default")
      (node (ref "OSC_B") (pin "2") (pinfunction "S_2") (pintype "passive"))
      (node (ref "R28") (pin "1") (pinfunction "1_1") (pintype "passive"))
    )
    (net (code "84") (name "Net-(Q1-B)") (class "Default")
      (node (ref "LOOP") (pin "5") (pinfunction "5_5") (pintype "bidirectional"))
      (node (ref "Q1") (pin "1") (pinfunction "B_1") (pintype "passive"))
      (node (ref "R12") (pin "2") (pinfunction "2_2") (pintype "passive"))
    )
    (net (code "85") (name "Net-(R3-Pad1)") (class "Default")
      (node (ref "R3") (pin "1") (pinfunction "1_1") (pintype "passive"))
      (node (ref "R7") (pin "1") (pinfunction "1_1") (pintype "passive"))
      (node (ref "R8") (pin "2") (pinfunction "2_2") (pintype "passive"))
    )
    (net (code "86") (name "Net-(R10-Pad1)") (class "Default")
      (node (ref "R10") (pin "1") (pinfunction "1_1") (pintype "passive"))
      (node (ref "R11") (pin "2") (pinfunction "2_2") (pintype "passive"))
      (node (ref "R8") (pin "1") (pinfunction "1_1") (pintype "passive"))
    )
    (net (code "87") (name "Net-(R40-Pad2)") (class "Default")
      (node (ref "R40") (pin "2") (pinfunction "2_2") (pintype "passive"))
      (node (ref "R41") (pin "1") (pinfunction "1_1") (pintype "passive"))
      (node (ref "R45") (pin "2") (pinfunction "2_2") (pintype "passive"))
      (node (ref "R52") (pin "2") (pinfunction "2_2") (pintype "passive"))
      (node (ref "R55") (pin "1") (pinfunction "1_1") (pintype "passive"))
    )
    (net (code "88") (name "Net-(RES-S)") (class "Default")
      (node (ref "R47") (pin "1") (pinfunction "1_1") (pintype "passive"))
      (node (ref "R53") (pin "2") (pinfunction "2_2") (pintype "passive"))
      (node (ref "RES") (pin "2") (pinfunction "S_2") (pintype "passive"))
    )
    (net (code "89") (name "Net-(RUN_A-S)") (class "Default")
      (node (ref "R20") (pin "1") (pinfunction "1_1") (pintype "passive"))
      (node (ref "RUN_A") (pin "2") (pinfunction "S_2") (pintype "passive"))
    )
    (net (code "90") (name "Net-(RUN_B-S)") (class "Default")
      (node (ref "R34") (pin "1") (pinfunction "1_1") (pintype "passive"))
      (node (ref "RUN_B") (pin "2") (pinfunction "S_2") (pintype "passive"))
    )
    (net (code "91") (name "Net-(RUN_CV-TIP)") (class "Default")
      (node (ref "R39") (pin "1") (pinfunction "1_1") (pintype "passive"))
      (node (ref "RUN_CV") (pin "P$1_TIP") (pinfunction "TIP_P$1_TIP") (pintype "passive"))
    )
    (net (code "92") (name "Net-(RUN_F-S)") (class "Default")
      (node (ref "R59") (pin "1") (pinfunction "1_1") (pintype "passive"))
      (node (ref "RUN_F") (pin "2") (pinfunction "S_2") (pintype "passive"))
    )
    (net (code "93") (name "VCC") (class "Default")
      (node (ref "C1") (pin "+") (pinfunction "+_+") (pintype "passive"))
      (node (ref "C2") (pin "1") (pinfunction "1_1") (pintype "passive"))
      (node (ref "C43") (pin "+") (pinfunction "+_+") (pintype "passive"))
      (node (ref "D1") (pin "C") (pinfunction "C_C") (pintype "passive"))
      (node (ref "IC1") (pin "3") (pinfunction "IN_3") (pintype "input"))
    )
    (net (code "94") (name "VEE") (class "Default")
      (node (ref "C12") (pin "-") (pinfunction "-_-") (pintype "passive"))
      (node (ref "C13") (pin "2") (pinfunction "2_2") (pintype "passive"))
      (node (ref "C44") (pin "-") (pinfunction "-_-") (pintype "passive"))
      (node (ref "D2") (pin "A") (pinfunction "A_A") (pintype "passive"))
      (node (ref "IC2") (pin "2") (pinfunction "IN_2") (pintype "bidirectional"))
    )
    (net (code "95") (name "unconnected-(BP-SWITCH-PadP$2_SWITCH)") (class "Default")
      (node (ref "BP") (pin "P$2_SWITCH") (pinfunction "SWITCH_P$2_SWITCH") (pintype "passive"))
    )
    (net (code "96") (name "unconnected-(CLOCK-SLEEVE-PadP$3_SLEEVE)") (class "Default")
      (node (ref "CLOCK") (pin "P$3_SLEEVE") (pinfunction "SLEEVE_P$3_SLEEVE") (pintype "passive"))
    )
    (net (code "97") (name "unconnected-(EXT_IN-SWITCH-PadP$2_SWITCH)") (class "Default")
      (node (ref "EXT_IN") (pin "P$2_SWITCH") (pinfunction "SWITCH_P$2_SWITCH") (pintype "passive"))
    )
    (net (code "98") (name "unconnected-(HP-SWITCH-PadP$2_SWITCH)") (class "Default")
      (node (ref "HP") (pin "P$2_SWITCH") (pinfunction "SWITCH_P$2_SWITCH") (pintype "passive"))
    )
    (net (code "99") (name "unconnected-(IC3A-P1-Pad7)") (class "Default")
      (node (ref "IC3") (pin "7") (pinfunction "P1_7") (pintype "input"))
    )
    (net (code "100") (name "unconnected-(IC3A-P2-Pad6)") (class "Default")
      (node (ref "IC3") (pin "6") (pinfunction "P2_6") (pintype "input"))
    )
    (net (code "101") (name "unconnected-(IC3A-P3-Pad5)") (class "Default")
      (node (ref "IC3") (pin "5") (pinfunction "P3_5") (pintype "input"))
    )
    (net (code "102") (name "unconnected-(IC3A-P4-Pad4)") (class "Default")
      (node (ref "IC3") (pin "4") (pinfunction "P4_4") (pintype "input"))
    )
    (net (code "103") (name "unconnected-(IC3A-P5-Pad13)") (class "Default")
      (node (ref "IC3") (pin "13") (pinfunction "P5_13") (pintype "input"))
    )
    (net (code "104") (name "unconnected-(IC3A-P6-Pad14)") (class "Default")
      (node (ref "IC3") (pin "14") (pinfunction "P6_14") (pintype "input"))
    )
    (net (code "105") (name "unconnected-(IC3A-P7-Pad15)") (class "Default")
      (node (ref "IC3") (pin "15") (pinfunction "P7_15") (pintype "input"))
    )
    (net (code "106") (name "unconnected-(IC3A-P8-Pad1)") (class "Default")
      (node (ref "IC3") (pin "1") (pinfunction "P8_1") (pintype "input"))
    )
    (net (code "107") (name "unconnected-(IC6E-MODE-Pad1)") (class "Default")
      (node (ref "IC6") (pin "1") (pinfunction "MODE_1") (pintype "input"))
    )
    (net (code "108") (name "unconnected-(LOOP-Pad1)") (class "Default")
      (node (ref "LOOP") (pin "1") (pinfunction "1_1") (pintype "bidirectional"))
    )
    (net (code "109") (name "unconnected-(LOOP-Pad6)") (class "Default")
      (node (ref "LOOP") (pin "6") (pinfunction "6_6") (pintype "bidirectional"))
    )
    (net (code "110") (name "unconnected-(LP-SWITCH-PadP$2_SWITCH)") (class "Default")
      (node (ref "LP") (pin "P$2_SWITCH") (pinfunction "SWITCH_P$2_SWITCH") (pintype "passive"))
    )
    (net (code "111") (name "unconnected-(PWM-SWITCH-PadP$2_SWITCH)") (class "Default")
      (node (ref "PWM") (pin "P$2_SWITCH") (pinfunction "SWITCH_P$2_SWITCH") (pintype "passive"))
    )
    (net (code "112") (name "unconnected-(P_A-SWITCH-PadP$2_SWITCH)") (class "Default")
      (node (ref "P_A") (pin "P$2_SWITCH") (pinfunction "SWITCH_P$2_SWITCH") (pintype "passive"))
    )
    (net (code "113") (name "unconnected-(P_B-SWITCH-PadP$2_SWITCH)") (class "Default")
      (node (ref "P_B") (pin "P$2_SWITCH") (pinfunction "SWITCH_P$2_SWITCH") (pintype "passive"))
    )
    (net (code "114") (name "unconnected-(RUN_CV-SWITCH-PadP$2_SWITCH)") (class "Default")
      (node (ref "RUN_CV") (pin "P$2_SWITCH") (pinfunction "SWITCH_P$2_SWITCH") (pintype "passive"))
    )
    (net (code "115") (name "unconnected-(T_A-SWITCH-PadP$2_SWITCH)") (class "Default")
      (node (ref "T_A") (pin "P$2_SWITCH") (pinfunction "SWITCH_P$2_SWITCH") (pintype "passive"))
    )
    (net (code "116") (name "unconnected-(T_B-SWITCH-PadP$2_SWITCH)") (class "Default")
      (node (ref "T_B") (pin "P$2_SWITCH") (pinfunction "SWITCH_P$2_SWITCH") (pintype "passive"))
    )
    (net (code "117") (name "unconnected-(XOR-SWITCH-PadP$2_SWITCH)") (class "Default")
      (node (ref "XOR") (pin "P$2_SWITCH") (pinfunction "SWITCH_P$2_SWITCH") (pintype "passive"))
    )
  )
)
